# mpu-9150_breakout.net
KiCad netlist of a schematic drawn in EAGLE
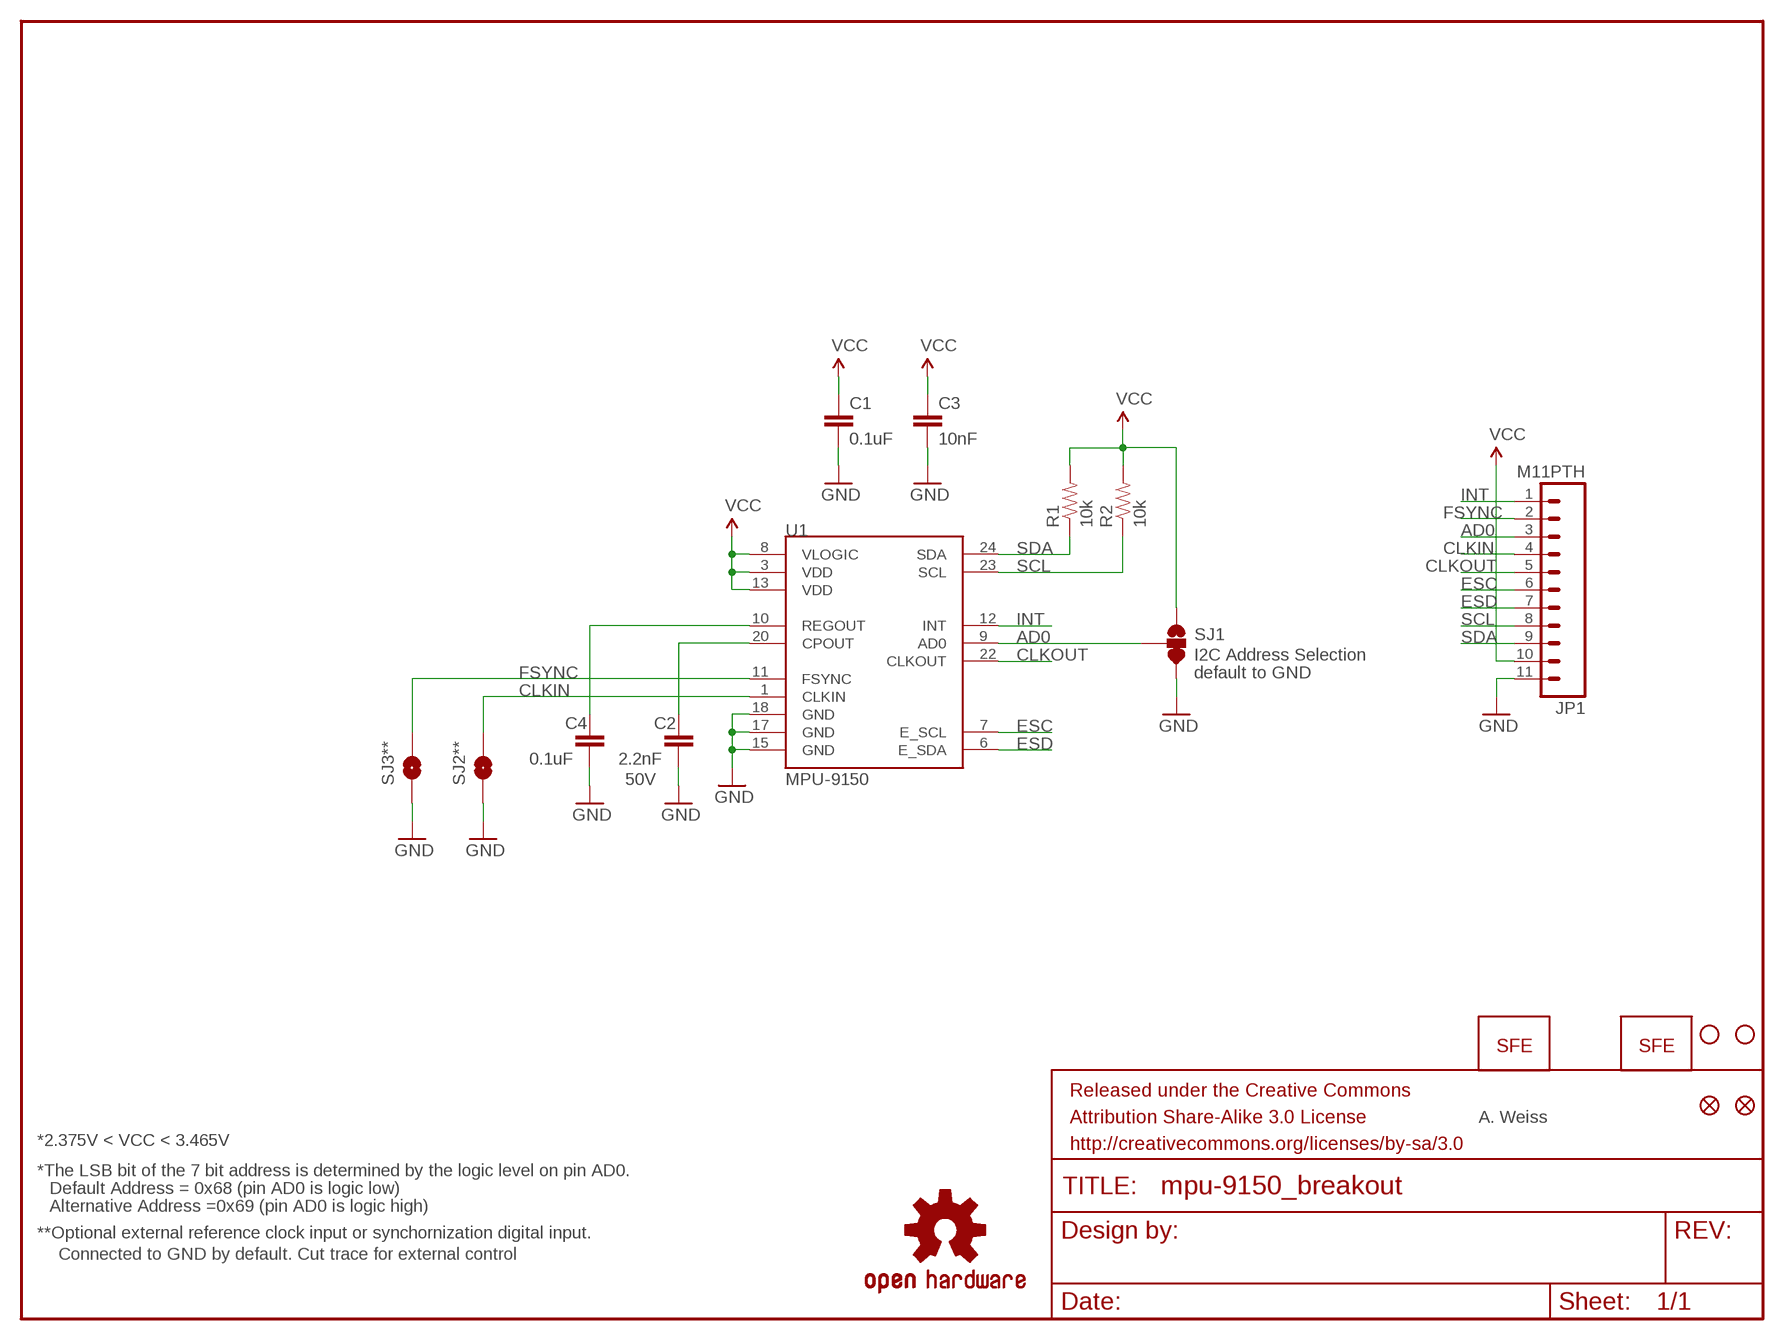
[diagram p0: schematic, sheet 1]

(export (version "E")
  (design (tool "Eeschema 10.0.6"))
  (components
    (comp (ref "C1")
      (value "0.1uF")
      (footprint "eagle-import:0402-CAP")
      (libsource (lib "eagle-import") (part "CAP0402-CAP"))
    )
    (comp (ref "C2")
      (value "2.2nF")
      (footprint "eagle-import:0402-CAP")
      (libsource (lib "eagle-import") (part "CAP0402-CAP"))
    )
    (comp (ref "C3")
      (value "10nF")
      (footprint "eagle-import:0402-CAP")
      (libsource (lib "eagle-import") (part "CAP0402-CAP"))
    )
    (comp (ref "C4")
      (value "0.1uF")
      (footprint "eagle-import:0402-CAP")
      (libsource (lib "eagle-import") (part "CAP0402-CAP"))
    )
    (comp (ref "JP1")
      (value "M11PTH")
      (footprint "eagle-import:1X11")
      (libsource (lib "eagle-import") (part "M11PTH"))
    )
    (comp (ref "JP2")
      (value "STAND-OFF")
      (footprint "eagle-import:STAND-OFF")
      (libsource (lib "eagle-import") (part "STAND-OFF"))
    )
    (comp (ref "JP3")
      (value "STAND-OFF")
      (footprint "eagle-import:STAND-OFF")
      (libsource (lib "eagle-import") (part "STAND-OFF"))
    )
    (comp (ref "JP4")
      (value "LOGO-SFENW2")
      (footprint "eagle-import:SFE-NEW-WEB")
      (libsource (lib "eagle-import") (part "LOGO-SFENW2"))
    )
    (comp (ref "JP6")
      (value "LOGO-SFESK")
      (footprint "eagle-import:SFE-LOGO-FLAME")
      (libsource (lib "eagle-import") (part "LOGO-SFESK"))
    )
    (comp (ref "JP7")
      (value "FIDUCIALUFIDUCIAL")
      (footprint "eagle-import:MICRO-FIDUCIAL")
      (libsource (lib "eagle-import") (part "FIDUCIALUFIDUCIAL"))
    )
    (comp (ref "JP8")
      (value "FIDUCIALUFIDUCIAL")
      (footprint "eagle-import:MICRO-FIDUCIAL")
      (libsource (lib "eagle-import") (part "FIDUCIALUFIDUCIAL"))
    )
    (comp (ref "R1")
      (value "10k")
      (footprint "eagle-import:0402-RES")
      (libsource (lib "eagle-import") (part "RESISTOR0402-RES"))
    )
    (comp (ref "R2")
      (value "10k")
      (footprint "eagle-import:0402-RES")
      (libsource (lib "eagle-import") (part "RESISTOR0402-RES"))
    )
    (comp (ref "SJ1")
      (value "SOLDERJUMPER_2WAYPASTE2&3")
      (footprint "eagle-import:SJ_3_PASTE2&3")
      (libsource (lib "eagle-import") (part "SOLDERJUMPER_2WAYPASTE2&3"))
    )
    (comp (ref "SJ2**")
      (value "SOLDERJUMPERTRACE")
      (footprint "eagle-import:SJ_2S-TRACE")
      (libsource (lib "eagle-import") (part "SOLDERJUMPERTRACE"))
    )
    (comp (ref "SJ3**")
      (value "SOLDERJUMPERTRACE")
      (footprint "eagle-import:SJ_2S-TRACE")
      (libsource (lib "eagle-import") (part "SOLDERJUMPERTRACE"))
    )
    (comp (ref "U$1")
      (value "OSHW-LOGOS")
      (footprint "eagle-import:OSHW-LOGO-S")
      (libsource (lib "eagle-import") (part "OSHW-LOGOS"))
    )
    (comp (ref "U1")
      (value "MPU-9150")
      (footprint "eagle-import:QFN-24-NP")
      (libsource (lib "eagle-import") (part "MPU-9150QFN-24-NP"))
    )
  )
  (nets
    (net (code "1") (name "/AD0") (class "Default")
      (node (ref "JP1") (pin "3") (pinfunction "3_3") (pintype "passive"))
      (node (ref "SJ1") (pin "2") (pinfunction "2_2") (pintype "passive"))
      (node (ref "U1") (pin "9") (pinfunction "AD0_9") (pintype "bidirectional"))
    )
    (net (code "2") (name "/CLKIN") (class "Default")
      (node (ref "JP1") (pin "4") (pinfunction "4_4") (pintype "passive"))
      (node (ref "SJ2**") (pin "2") (pinfunction "2_2") (pintype "passive"))
      (node (ref "U1") (pin "1") (pinfunction "CLKIN_1") (pintype "bidirectional"))
    )
    (net (code "3") (name "/CLKOUT") (class "Default")
      (node (ref "JP1") (pin "5") (pinfunction "5_5") (pintype "passive"))
      (node (ref "U1") (pin "22") (pinfunction "CLKOUT_22") (pintype "bidirectional"))
    )
    (net (code "4") (name "/ESC") (class "Default")
      (node (ref "JP1") (pin "6") (pinfunction "6_6") (pintype "passive"))
      (node (ref "U1") (pin "7") (pinfunction "E_SCL_7") (pintype "bidirectional"))
    )
    (net (code "5") (name "/ESD") (class "Default")
      (node (ref "JP1") (pin "7") (pinfunction "7_7") (pintype "passive"))
      (node (ref "U1") (pin "6") (pinfunction "E_SDA_6") (pintype "bidirectional"))
    )
    (net (code "6") (name "/FSYNC") (class "Default")
      (node (ref "JP1") (pin "2") (pinfunction "2_2") (pintype "passive"))
      (node (ref "SJ3**") (pin "2") (pinfunction "2_2") (pintype "passive"))
      (node (ref "U1") (pin "11") (pinfunction "FSYNC_11") (pintype "bidirectional"))
    )
    (net (code "7") (name "/INT") (class "Default")
      (node (ref "JP1") (pin "1") (pinfunction "1_1") (pintype "passive"))
      (node (ref "U1") (pin "12") (pinfunction "INT_12") (pintype "bidirectional"))
    )
    (net (code "8") (name "/SCL") (class "Default")
      (node (ref "JP1") (pin "8") (pinfunction "8_8") (pintype "passive"))
      (node (ref "R2") (pin "1") (pinfunction "1_1") (pintype "passive"))
      (node (ref "U1") (pin "23") (pinfunction "SCL_23") (pintype "bidirectional"))
    )
    (net (code "9") (name "/SDA") (class "Default")
      (node (ref "JP1") (pin "9") (pinfunction "9_9") (pintype "passive"))
      (node (ref "R1") (pin "1") (pinfunction "1_1") (pintype "passive"))
      (node (ref "U1") (pin "24") (pinfunction "SDA_24") (pintype "bidirectional"))
    )
    (net (code "10") (name "GND") (class "Default")
      (node (ref "C1") (pin "2") (pinfunction "2_2") (pintype "passive"))
      (node (ref "C2") (pin "2") (pinfunction "2_2") (pintype "passive"))
      (node (ref "C3") (pin "2") (pinfunction "2_2") (pintype "passive"))
      (node (ref "C4") (pin "2") (pinfunction "2_2") (pintype "passive"))
      (node (ref "JP1") (pin "11") (pinfunction "11_11") (pintype "passive"))
      (node (ref "SJ1") (pin "3") (pinfunction "3_3") (pintype "passive"))
      (node (ref "SJ2**") (pin "1") (pinfunction "1_1") (pintype "passive"))
      (node (ref "SJ3**") (pin "1") (pinfunction "1_1") (pintype "passive"))
      (node (ref "U1") (pin "15") (pinfunction "GND_15") (pintype "bidirectional"))
      (node (ref "U1") (pin "17") (pinfunction "GND_17") (pintype "bidirectional"))
      (node (ref "U1") (pin "18") (pinfunction "GND_18") (pintype "bidirectional"))
    )
    (net (code "11") (name "Net-(U1-CPOUT)") (class "Default")
      (node (ref "C2") (pin "1") (pinfunction "1_1") (pintype "passive"))
      (node (ref "U1") (pin "20") (pinfunction "CPOUT_20") (pintype "bidirectional"))
    )
    (net (code "12") (name "Net-(U1-REGOUT)") (class "Default")
      (node (ref "C4") (pin "1") (pinfunction "1_1") (pintype "passive"))
      (node (ref "U1") (pin "10") (pinfunction "REGOUT_10") (pintype "bidirectional"))
    )
    (net (code "13") (name "VCC") (class "Default")
      (node (ref "C1") (pin "1") (pinfunction "1_1") (pintype "passive"))
      (node (ref "C3") (pin "1") (pinfunction "1_1") (pintype "passive"))
      (node (ref "JP1") (pin "10") (pinfunction "10_10") (pintype "passive"))
      (node (ref "R1") (pin "2") (pinfunction "2_2") (pintype "passive"))
      (node (ref "R2") (pin "2") (pinfunction "2_2") (pintype "passive"))
      (node (ref "SJ1") (pin "1") (pinfunction "1_1") (pintype "passive"))
      (node (ref "U1") (pin "13") (pinfunction "VDD_13") (pintype "bidirectional"))
      (node (ref "U1") (pin "3") (pinfunction "VDD_3") (pintype "bidirectional"))
      (node (ref "U1") (pin "8") (pinfunction "VLOGIC_8") (pintype "bidirectional"))
    )
  )
)
